# Display.net
KiCad netlist of a schematic drawn in Altium Designer
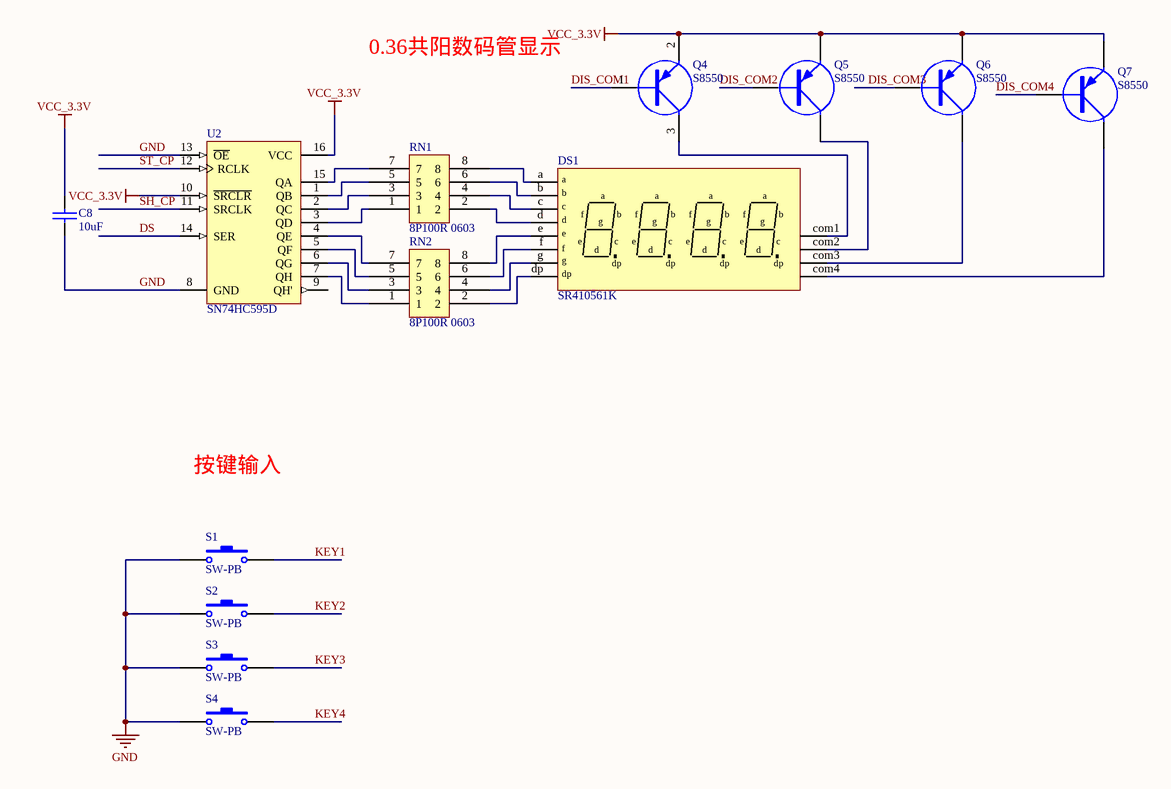
[diagram p0: Display.SchDoc]

(export (version "E")
  (design (tool "Eeschema 10.0.6"))
  (components
    (comp (ref "C8")
      (value "10uF")
      (footprint "0805c")
      (description "Capacitor")
      (libsource (lib "SM") (part "CAP"))
    )
    (comp (ref "DS1")
      (value "SR410561K")
      (footprint "SR410361")
      (description "CP-SR410561K")
      (libsource (lib "光电器件") (part "SR410561K"))
    )
    (comp (ref "Q4")
      (value "S8550")
      (footprint "SOT-23_B")
      (description "PNP Transistor")
      (libsource (lib "") (part "PNP_1"))
    )
    (comp (ref "Q5")
      (value "S8550")
      (footprint "SOT-23_B")
      (description "PNP Transistor")
      (libsource (lib "SM") (part "PNP"))
    )
    (comp (ref "Q6")
      (value "S8550")
      (footprint "SOT-23_B")
      (description "PNP Transistor")
      (libsource (lib "SM") (part "PNP"))
    )
    (comp (ref "Q7")
      (value "S8550")
      (footprint "SOT-23_B")
      (description "PNP Transistor")
      (libsource (lib "SM") (part "PNP"))
    )
    (comp (ref "RN1")
      (value "8P100R 0603")
      (footprint "8P4R_0603")
      (libsource (lib "SMD电阻") (part "8P4R 0603"))
    )
    (comp (ref "RN2")
      (value "8P100R 0603")
      (footprint "8P4R_0603")
      (libsource (lib "SMD电阻") (part "8P4R 0603"))
    )
    (comp (ref "S1")
      (value "SW-PB")
      (footprint "BUTTON_SMT_6*6")
      (description "Switch")
      (fields (field (name "PUBLISHER") "Altium Limited"))
      (libsource (lib "其他元器件") (part "SW-PB"))
    )
    (comp (ref "S2")
      (value "SW-PB")
      (footprint "BUTTON_SMT_6*6")
      (description "Switch")
      (fields (field (name "PUBLISHER") "Altium Limited"))
      (libsource (lib "其他元器件") (part "SW-PB"))
    )
    (comp (ref "S3")
      (value "SW-PB")
      (footprint "BUTTON_SMT_6*6")
      (description "Switch")
      (fields (field (name "PUBLISHER") "Altium Limited"))
      (libsource (lib "其他元器件") (part "SW-PB"))
    )
    (comp (ref "S4")
      (value "SW-PB")
      (footprint "BUTTON_SMT_6*6")
      (description "Switch")
      (fields (field (name "PUBLISHER") "Altium Limited"))
      (libsource (lib "其他元器件") (part "SW-PB"))
    )
    (comp (ref "U2")
      (value "SN74HC595D")
      (footprint "SO-16N")
      (description "8-Bit Shift Register with 3-State Output Registers")
      (fields (field (name "PUBLISHER") "Altium Limited"))
      (libsource (lib "TI Logic Register") (part "SN74HC595D"))
    )
  )
  (nets
    (net (code "1") (name "/DIS_COM1") (class "Default")
      (node (ref "Q4") (pin "1") (pinfunction "B_1") (pintype "passive"))
    )
    (net (code "2") (name "/DIS_COM2") (class "Default")
      (node (ref "Q5") (pin "1") (pinfunction "B_1") (pintype "passive"))
    )
    (net (code "3") (name "/DIS_COM3") (class "Default")
      (node (ref "Q6") (pin "1") (pinfunction "B_1") (pintype "passive"))
    )
    (net (code "4") (name "/DIS_COM4") (class "Default")
      (node (ref "Q7") (pin "1") (pinfunction "B_1") (pintype "passive"))
    )
    (net (code "5") (name "/DS") (class "Default")
      (node (ref "U2") (pin "14") (pinfunction "SER_14") (pintype "input"))
    )
    (net (code "6") (name "/KEY1") (class "Default")
      (node (ref "S1") (pin "2") (pinfunction "2_2") (pintype "passive"))
    )
    (net (code "7") (name "/KEY2") (class "Default")
      (node (ref "S2") (pin "2") (pinfunction "2_2") (pintype "passive"))
    )
    (net (code "8") (name "/KEY3") (class "Default")
      (node (ref "S3") (pin "2") (pinfunction "2_2") (pintype "passive"))
    )
    (net (code "9") (name "/KEY4") (class "Default")
      (node (ref "S4") (pin "2") (pinfunction "2_2") (pintype "passive"))
    )
    (net (code "10") (name "/SH_CP") (class "Default")
      (node (ref "U2") (pin "11") (pinfunction "SRCLK_11") (pintype "input"))
    )
    (net (code "11") (name "/ST_CP") (class "Default")
      (node (ref "U2") (pin "12") (pinfunction "RCLK_12") (pintype "input"))
    )
    (net (code "12") (name "GND") (class "Default")
      (node (ref "C8") (pin "1") (pinfunction "1_1") (pintype "passive"))
      (node (ref "S1") (pin "1") (pinfunction "1_1") (pintype "passive"))
      (node (ref "S2") (pin "1") (pinfunction "1_1") (pintype "passive"))
      (node (ref "S3") (pin "1") (pinfunction "1_1") (pintype "passive"))
      (node (ref "S4") (pin "1") (pinfunction "1_1") (pintype "passive"))
      (node (ref "U2") (pin "13") (pinfunction "~{OE}_13") (pintype "input"))
      (node (ref "U2") (pin "8") (pinfunction "GND_8") (pintype "power_in"))
    )
    (net (code "13") (name "Net-(DS1-Pada)") (class "Default")
      (node (ref "DS1") (pin "a") (pinfunction "a_a") (pintype "passive"))
      (node (ref "RN1") (pin "8") (pinfunction "8_8") (pintype "passive"))
    )
    (net (code "14") (name "Net-(DS1-Padb)") (class "Default")
      (node (ref "DS1") (pin "b") (pinfunction "b_b") (pintype "passive"))
      (node (ref "RN1") (pin "6") (pinfunction "6_6") (pintype "passive"))
    )
    (net (code "15") (name "Net-(DS1-Padc)") (class "Default")
      (node (ref "DS1") (pin "c") (pinfunction "c_c") (pintype "passive"))
      (node (ref "RN1") (pin "4") (pinfunction "4_4") (pintype "passive"))
    )
    (net (code "16") (name "Net-(DS1-Padd)") (class "Default")
      (node (ref "DS1") (pin "d") (pinfunction "d_d") (pintype "passive"))
      (node (ref "RN1") (pin "2") (pinfunction "2_2") (pintype "passive"))
    )
    (net (code "17") (name "Net-(DS1-Paddp)") (class "Default")
      (node (ref "DS1") (pin "dp") (pinfunction "dp_dp") (pintype "passive"))
      (node (ref "RN2") (pin "2") (pinfunction "2_2") (pintype "passive"))
    )
    (net (code "18") (name "Net-(DS1-Pade)") (class "Default")
      (node (ref "DS1") (pin "e") (pinfunction "e_e") (pintype "passive"))
      (node (ref "RN2") (pin "8") (pinfunction "8_8") (pintype "passive"))
    )
    (net (code "19") (name "Net-(DS1-Padf)") (class "Default")
      (node (ref "DS1") (pin "f") (pinfunction "f_f") (pintype "passive"))
      (node (ref "RN2") (pin "6") (pinfunction "6_6") (pintype "passive"))
    )
    (net (code "20") (name "Net-(DS1-Padg)") (class "Default")
      (node (ref "DS1") (pin "g") (pinfunction "g_g") (pintype "passive"))
      (node (ref "RN2") (pin "4") (pinfunction "4_4") (pintype "passive"))
    )
    (net (code "21") (name "Net-(Q4-C)") (class "Default")
      (node (ref "DS1") (pin "com1") (pinfunction "com1_com1") (pintype "passive"))
      (node (ref "Q4") (pin "3") (pinfunction "C_3") (pintype "passive"))
    )
    (net (code "22") (name "Net-(Q5-C)") (class "Default")
      (node (ref "DS1") (pin "com2") (pinfunction "com2_com2") (pintype "passive"))
      (node (ref "Q5") (pin "3") (pinfunction "C_3") (pintype "passive"))
    )
    (net (code "23") (name "Net-(Q6-C)") (class "Default")
      (node (ref "DS1") (pin "com3") (pinfunction "com3_com3") (pintype "passive"))
      (node (ref "Q6") (pin "3") (pinfunction "C_3") (pintype "passive"))
    )
    (net (code "24") (name "Net-(Q7-C)") (class "Default")
      (node (ref "DS1") (pin "com4") (pinfunction "com4_com4") (pintype "passive"))
      (node (ref "Q7") (pin "3") (pinfunction "C_3") (pintype "passive"))
    )
    (net (code "25") (name "Net-(U2-QA)") (class "Default")
      (node (ref "RN1") (pin "7") (pinfunction "7_7") (pintype "passive"))
      (node (ref "U2") (pin "15") (pinfunction "QA_15") (pintype "tri_state"))
    )
    (net (code "26") (name "Net-(U2-QB)") (class "Default")
      (node (ref "RN1") (pin "5") (pinfunction "5_5") (pintype "passive"))
      (node (ref "U2") (pin "1") (pinfunction "QB_1") (pintype "tri_state"))
    )
    (net (code "27") (name "Net-(U2-QC)") (class "Default")
      (node (ref "RN1") (pin "3") (pinfunction "3_3") (pintype "passive"))
      (node (ref "U2") (pin "2") (pinfunction "QC_2") (pintype "tri_state"))
    )
    (net (code "28") (name "Net-(U2-QD)") (class "Default")
      (node (ref "RN1") (pin "1") (pinfunction "1_1") (pintype "passive"))
      (node (ref "U2") (pin "3") (pinfunction "QD_3") (pintype "tri_state"))
    )
    (net (code "29") (name "Net-(U2-QE)") (class "Default")
      (node (ref "RN2") (pin "7") (pinfunction "7_7") (pintype "passive"))
      (node (ref "U2") (pin "4") (pinfunction "QE_4") (pintype "tri_state"))
    )
    (net (code "30") (name "Net-(U2-QF)") (class "Default")
      (node (ref "RN2") (pin "5") (pinfunction "5_5") (pintype "passive"))
      (node (ref "U2") (pin "5") (pinfunction "QF_5") (pintype "tri_state"))
    )
    (net (code "31") (name "Net-(U2-QG)") (class "Default")
      (node (ref "RN2") (pin "3") (pinfunction "3_3") (pintype "passive"))
      (node (ref "U2") (pin "6") (pinfunction "QG_6") (pintype "tri_state"))
    )
    (net (code "32") (name "Net-(U2-QH)") (class "Default")
      (node (ref "RN2") (pin "1") (pinfunction "1_1") (pintype "passive"))
      (node (ref "U2") (pin "7") (pinfunction "QH_7") (pintype "tri_state"))
    )
    (net (code "33") (name "VCC_3.3V") (class "Default")
      (node (ref "C8") (pin "2") (pinfunction "2_2") (pintype "passive"))
      (node (ref "Q4") (pin "2") (pinfunction "E_2") (pintype "passive"))
      (node (ref "Q5") (pin "2") (pinfunction "E_2") (pintype "passive"))
      (node (ref "Q6") (pin "2") (pinfunction "E_2") (pintype "passive"))
      (node (ref "Q7") (pin "2") (pinfunction "E_2") (pintype "passive"))
      (node (ref "U2") (pin "10") (pinfunction "~{SRCLR}_10") (pintype "input"))
      (node (ref "U2") (pin "16") (pinfunction "VCC_16") (pintype "power_in"))
    )
    (net (code "34") (name "unconnected-(U2-QH'-Pad9)") (class "Default")
      (node (ref "U2") (pin "9") (pinfunction "QH'_9") (pintype "output"))
    )
  )
)
